# beaglebone.net
KiCad netlist of a schematic drawn in Altium Designer
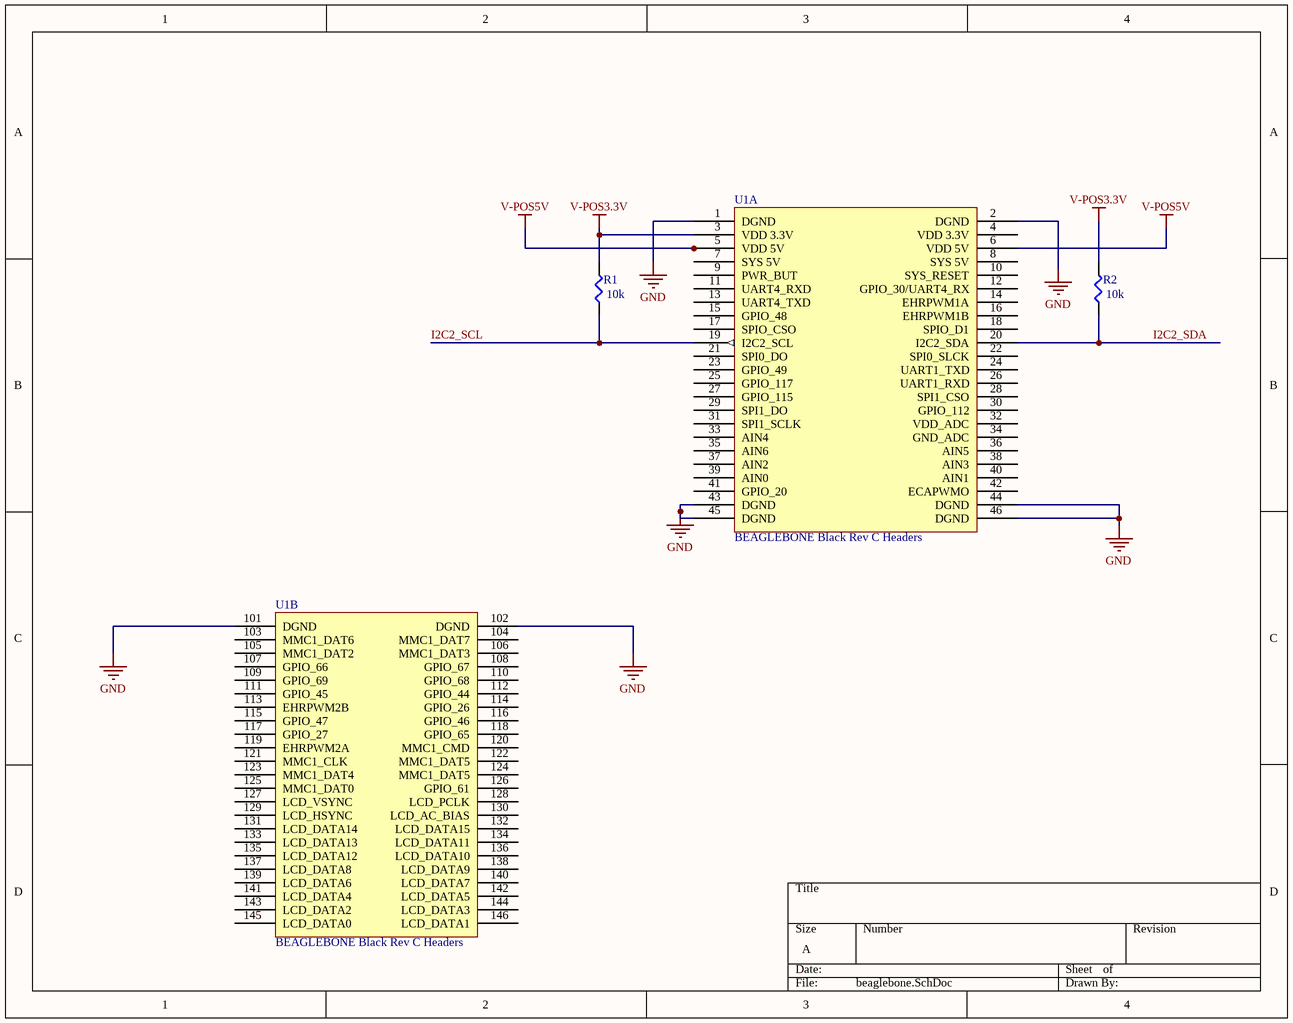
[diagram p0: beaglebone.SchDoc]

(export (version "E")
  (design (tool "Eeschema 10.0.6"))
  (components
    (comp (ref "R1")
      (value "10k")
      (footprint "SMD-0805-RES")
      (description "RES SMD 10K OHM 1% 1/8W 0805")
      (fields
        (field (name "PART NUMBER") "ERJ-6ENF1002V")
        (field (name "DIGI-KEY PART NUMBER") "P10.0KCCT-ND")
      )
      (libsource (lib "resistors") (part "ERJ-6ENF1002V"))
    )
    (comp (ref "R2")
      (value "10k")
      (footprint "SMD-0805-RES")
      (description "RES SMD 10K OHM 1% 1/8W 0805")
      (fields
        (field (name "PART NUMBER") "ERJ-6ENF1002V")
        (field (name "DIGI-KEY PART NUMBER") "P10.0KCCT-ND")
      )
      (libsource (lib "resistors") (part "ERJ-6ENF1002V"))
    )
    (comp (ref "U1")
      (value "BEAGLEBONE Black Rev C Headers")
      (footprint "Beaglebone_Topside")
      (description "KIT DEV BEAGLEBONE BLACK REV C. Header Breakout")
      (libsource (lib "misc") (part "Beaglebone"))
    )
  )
  (nets
    (net (code "1") (name "/I2C2_SCL") (class "Default")
      (node (ref "R1") (pin "1") (pinfunction "1_1") (pintype "passive"))
      (node (ref "U1") (pin "19") (pinfunction "I2C2_SCL_19") (pintype "output"))
    )
    (net (code "2") (name "/I2C2_SDA") (class "Default")
      (node (ref "R2") (pin "1") (pinfunction "1_1") (pintype "passive"))
      (node (ref "U1") (pin "20") (pinfunction "I2C2_SDA_20") (pintype "passive"))
    )
    (net (code "3") (name "GND") (class "Default")
      (node (ref "U1") (pin "1") (pinfunction "DGND_1") (pintype "passive"))
      (node (ref "U1") (pin "101") (pinfunction "DGND_101") (pintype "passive"))
      (node (ref "U1") (pin "102") (pinfunction "DGND_102") (pintype "passive"))
      (node (ref "U1") (pin "2") (pinfunction "DGND_2") (pintype "passive"))
      (node (ref "U1") (pin "43") (pinfunction "DGND_43") (pintype "passive"))
      (node (ref "U1") (pin "44") (pinfunction "DGND_44") (pintype "passive"))
      (node (ref "U1") (pin "45") (pinfunction "DGND_45") (pintype "passive"))
      (node (ref "U1") (pin "46") (pinfunction "DGND_46") (pintype "passive"))
    )
    (net (code "4") (name "V-POS3.3V") (class "Default")
      (node (ref "R1") (pin "2") (pinfunction "2_2") (pintype "passive"))
      (node (ref "R2") (pin "2") (pinfunction "2_2") (pintype "passive"))
      (node (ref "U1") (pin "3") (pinfunction "VDD_3.3V_3") (pintype "passive"))
    )
    (net (code "5") (name "V-POS5V") (class "Default")
      (node (ref "U1") (pin "5") (pinfunction "VDD_5V_5") (pintype "passive"))
      (node (ref "U1") (pin "6") (pinfunction "VDD_5V_6") (pintype "passive"))
    )
    (net (code "6") (name "unconnected-(U1A-AIN0-Pad39)") (class "Default")
      (node (ref "U1") (pin "39") (pinfunction "AIN0_39") (pintype "passive"))
    )
    (net (code "7") (name "unconnected-(U1A-AIN1-Pad40)") (class "Default")
      (node (ref "U1") (pin "40") (pinfunction "AIN1_40") (pintype "passive"))
    )
    (net (code "8") (name "unconnected-(U1A-AIN2-Pad37)") (class "Default")
      (node (ref "U1") (pin "37") (pinfunction "AIN2_37") (pintype "passive"))
    )
    (net (code "9") (name "unconnected-(U1A-AIN3-Pad38)") (class "Default")
      (node (ref "U1") (pin "38") (pinfunction "AIN3_38") (pintype "passive"))
    )
    (net (code "10") (name "unconnected-(U1A-AIN4-Pad33)") (class "Default")
      (node (ref "U1") (pin "33") (pinfunction "AIN4_33") (pintype "passive"))
    )
    (net (code "11") (name "unconnected-(U1A-AIN5-Pad36)") (class "Default")
      (node (ref "U1") (pin "36") (pinfunction "AIN5_36") (pintype "passive"))
    )
    (net (code "12") (name "unconnected-(U1A-AIN6-Pad35)") (class "Default")
      (node (ref "U1") (pin "35") (pinfunction "AIN6_35") (pintype "passive"))
    )
    (net (code "13") (name "unconnected-(U1A-ECAPWMO-Pad42)") (class "Default")
      (node (ref "U1") (pin "42") (pinfunction "ECAPWMO_42") (pintype "passive"))
    )
    (net (code "14") (name "unconnected-(U1A-EHRPWM1A-Pad14)") (class "Default")
      (node (ref "U1") (pin "14") (pinfunction "EHRPWM1A_14") (pintype "passive"))
    )
    (net (code "15") (name "unconnected-(U1A-EHRPWM1B-Pad16)") (class "Default")
      (node (ref "U1") (pin "16") (pinfunction "EHRPWM1B_16") (pintype "passive"))
    )
    (net (code "16") (name "unconnected-(U1A-GND_ADC-Pad34)") (class "Default")
      (node (ref "U1") (pin "34") (pinfunction "GND_ADC_34") (pintype "passive"))
    )
    (net (code "17") (name "unconnected-(U1A-GPIO_20-Pad41)") (class "Default")
      (node (ref "U1") (pin "41") (pinfunction "GPIO_20_41") (pintype "passive"))
    )
    (net (code "18") (name "unconnected-(U1A-GPIO_30{slash}UART4_RX-Pad12)") (class "Default")
      (node (ref "U1") (pin "12") (pinfunction "GPIO_30/UART4_RX_12") (pintype "passive"))
    )
    (net (code "19") (name "unconnected-(U1A-GPIO_48-Pad15)") (class "Default")
      (node (ref "U1") (pin "15") (pinfunction "GPIO_48_15") (pintype "passive"))
    )
    (net (code "20") (name "unconnected-(U1A-GPIO_49-Pad23)") (class "Default")
      (node (ref "U1") (pin "23") (pinfunction "GPIO_49_23") (pintype "passive"))
    )
    (net (code "21") (name "unconnected-(U1A-GPIO_112-Pad30)") (class "Default")
      (node (ref "U1") (pin "30") (pinfunction "GPIO_112_30") (pintype "passive"))
    )
    (net (code "22") (name "unconnected-(U1A-GPIO_115-Pad27)") (class "Default")
      (node (ref "U1") (pin "27") (pinfunction "GPIO_115_27") (pintype "passive"))
    )
    (net (code "23") (name "unconnected-(U1A-GPIO_117-Pad25)") (class "Default")
      (node (ref "U1") (pin "25") (pinfunction "GPIO_117_25") (pintype "passive"))
    )
    (net (code "24") (name "unconnected-(U1A-PWR_BUT-Pad9)") (class "Default")
      (node (ref "U1") (pin "9") (pinfunction "PWR_BUT_9") (pintype "passive"))
    )
    (net (code "25") (name "unconnected-(U1A-SPI0_DO-Pad21)") (class "Default")
      (node (ref "U1") (pin "21") (pinfunction "SPI0_DO_21") (pintype "passive"))
    )
    (net (code "26") (name "unconnected-(U1A-SPI0_SLCK-Pad22)") (class "Default")
      (node (ref "U1") (pin "22") (pinfunction "SPI0_SLCK_22") (pintype "passive"))
    )
    (net (code "27") (name "unconnected-(U1A-SPI1_CSO-Pad28)") (class "Default")
      (node (ref "U1") (pin "28") (pinfunction "SPI1_CSO_28") (pintype "passive"))
    )
    (net (code "28") (name "unconnected-(U1A-SPI1_DO-Pad29)") (class "Default")
      (node (ref "U1") (pin "29") (pinfunction "SPI1_DO_29") (pintype "passive"))
    )
    (net (code "29") (name "unconnected-(U1A-SPI1_SCLK-Pad31)") (class "Default")
      (node (ref "U1") (pin "31") (pinfunction "SPI1_SCLK_31") (pintype "passive"))
    )
    (net (code "30") (name "unconnected-(U1A-SPIO_CSO-Pad17)") (class "Default")
      (node (ref "U1") (pin "17") (pinfunction "SPIO_CSO_17") (pintype "passive"))
    )
    (net (code "31") (name "unconnected-(U1A-SPIO_D1-Pad18)") (class "Default")
      (node (ref "U1") (pin "18") (pinfunction "SPIO_D1_18") (pintype "passive"))
    )
    (net (code "32") (name "unconnected-(U1A-SYS_5V-Pad7)") (class "Default")
      (node (ref "U1") (pin "7") (pinfunction "SYS_5V_7") (pintype "passive"))
    )
    (net (code "33") (name "unconnected-(U1A-SYS_5V-Pad8)") (class "Default")
      (node (ref "U1") (pin "8") (pinfunction "SYS_5V_8") (pintype "passive"))
    )
    (net (code "34") (name "unconnected-(U1A-SYS_RESET-Pad10)") (class "Default")
      (node (ref "U1") (pin "10") (pinfunction "SYS_RESET_10") (pintype "passive"))
    )
    (net (code "35") (name "unconnected-(U1A-UART1_RXD-Pad26)") (class "Default")
      (node (ref "U1") (pin "26") (pinfunction "UART1_RXD_26") (pintype "passive"))
    )
    (net (code "36") (name "unconnected-(U1A-UART1_TXD-Pad24)") (class "Default")
      (node (ref "U1") (pin "24") (pinfunction "UART1_TXD_24") (pintype "passive"))
    )
    (net (code "37") (name "unconnected-(U1A-UART4_RXD-Pad11)") (class "Default")
      (node (ref "U1") (pin "11") (pinfunction "UART4_RXD_11") (pintype "passive"))
    )
    (net (code "38") (name "unconnected-(U1A-UART4_TXD-Pad13)") (class "Default")
      (node (ref "U1") (pin "13") (pinfunction "UART4_TXD_13") (pintype "passive"))
    )
    (net (code "39") (name "unconnected-(U1A-VDD_3.3V-Pad4)") (class "Default")
      (node (ref "U1") (pin "4") (pinfunction "VDD_3.3V_4") (pintype "passive"))
    )
    (net (code "40") (name "unconnected-(U1A-VDD_ADC-Pad32)") (class "Default")
      (node (ref "U1") (pin "32") (pinfunction "VDD_ADC_32") (pintype "passive"))
    )
    (net (code "41") (name "unconnected-(U1B-EHRPWM2A-Pad119)") (class "Default")
      (node (ref "U1") (pin "119") (pinfunction "EHRPWM2A_119") (pintype "passive"))
    )
    (net (code "42") (name "unconnected-(U1B-EHRPWM2B-Pad113)") (class "Default")
      (node (ref "U1") (pin "113") (pinfunction "EHRPWM2B_113") (pintype "passive"))
    )
    (net (code "43") (name "unconnected-(U1B-GPIO_26-Pad114)") (class "Default")
      (node (ref "U1") (pin "114") (pinfunction "GPIO_26_114") (pintype "passive"))
    )
    (net (code "44") (name "unconnected-(U1B-GPIO_27-Pad117)") (class "Default")
      (node (ref "U1") (pin "117") (pinfunction "GPIO_27_117") (pintype "passive"))
    )
    (net (code "45") (name "unconnected-(U1B-GPIO_44-Pad112)") (class "Default")
      (node (ref "U1") (pin "112") (pinfunction "GPIO_44_112") (pintype "passive"))
    )
    (net (code "46") (name "unconnected-(U1B-GPIO_45-Pad111)") (class "Default")
      (node (ref "U1") (pin "111") (pinfunction "GPIO_45_111") (pintype "passive"))
    )
    (net (code "47") (name "unconnected-(U1B-GPIO_46-Pad116)") (class "Default")
      (node (ref "U1") (pin "116") (pinfunction "GPIO_46_116") (pintype "passive"))
    )
    (net (code "48") (name "unconnected-(U1B-GPIO_47-Pad115)") (class "Default")
      (node (ref "U1") (pin "115") (pinfunction "GPIO_47_115") (pintype "passive"))
    )
    (net (code "49") (name "unconnected-(U1B-GPIO_61-Pad126)") (class "Default")
      (node (ref "U1") (pin "126") (pinfunction "GPIO_61_126") (pintype "passive"))
    )
    (net (code "50") (name "unconnected-(U1B-GPIO_65-Pad118)") (class "Default")
      (node (ref "U1") (pin "118") (pinfunction "GPIO_65_118") (pintype "passive"))
    )
    (net (code "51") (name "unconnected-(U1B-GPIO_66-Pad107)") (class "Default")
      (node (ref "U1") (pin "107") (pinfunction "GPIO_66_107") (pintype "passive"))
    )
    (net (code "52") (name "unconnected-(U1B-GPIO_67-Pad108)") (class "Default")
      (node (ref "U1") (pin "108") (pinfunction "GPIO_67_108") (pintype "passive"))
    )
    (net (code "53") (name "unconnected-(U1B-GPIO_68-Pad110)") (class "Default")
      (node (ref "U1") (pin "110") (pinfunction "GPIO_68_110") (pintype "passive"))
    )
    (net (code "54") (name "unconnected-(U1B-GPIO_69-Pad109)") (class "Default")
      (node (ref "U1") (pin "109") (pinfunction "GPIO_69_109") (pintype "passive"))
    )
    (net (code "55") (name "unconnected-(U1B-LCD_AC_BIAS-Pad130)") (class "Default")
      (node (ref "U1") (pin "130") (pinfunction "LCD_AC_BIAS_130") (pintype "passive"))
    )
    (net (code "56") (name "unconnected-(U1B-LCD_DATA0-Pad145)") (class "Default")
      (node (ref "U1") (pin "145") (pinfunction "LCD_DATA0_145") (pintype "passive"))
    )
    (net (code "57") (name "unconnected-(U1B-LCD_DATA1-Pad146)") (class "Default")
      (node (ref "U1") (pin "146") (pinfunction "LCD_DATA1_146") (pintype "passive"))
    )
    (net (code "58") (name "unconnected-(U1B-LCD_DATA2-Pad143)") (class "Default")
      (node (ref "U1") (pin "143") (pinfunction "LCD_DATA2_143") (pintype "passive"))
    )
    (net (code "59") (name "unconnected-(U1B-LCD_DATA3-Pad144)") (class "Default")
      (node (ref "U1") (pin "144") (pinfunction "LCD_DATA3_144") (pintype "passive"))
    )
    (net (code "60") (name "unconnected-(U1B-LCD_DATA4-Pad141)") (class "Default")
      (node (ref "U1") (pin "141") (pinfunction "LCD_DATA4_141") (pintype "passive"))
    )
    (net (code "61") (name "unconnected-(U1B-LCD_DATA5-Pad142)") (class "Default")
      (node (ref "U1") (pin "142") (pinfunction "LCD_DATA5_142") (pintype "passive"))
    )
    (net (code "62") (name "unconnected-(U1B-LCD_DATA6-Pad139)") (class "Default")
      (node (ref "U1") (pin "139") (pinfunction "LCD_DATA6_139") (pintype "passive"))
    )
    (net (code "63") (name "unconnected-(U1B-LCD_DATA7-Pad140)") (class "Default")
      (node (ref "U1") (pin "140") (pinfunction "LCD_DATA7_140") (pintype "passive"))
    )
    (net (code "64") (name "unconnected-(U1B-LCD_DATA8-Pad137)") (class "Default")
      (node (ref "U1") (pin "137") (pinfunction "LCD_DATA8_137") (pintype "passive"))
    )
    (net (code "65") (name "unconnected-(U1B-LCD_DATA9-Pad138)") (class "Default")
      (node (ref "U1") (pin "138") (pinfunction "LCD_DATA9_138") (pintype "passive"))
    )
    (net (code "66") (name "unconnected-(U1B-LCD_DATA10-Pad136)") (class "Default")
      (node (ref "U1") (pin "136") (pinfunction "LCD_DATA10_136") (pintype "passive"))
    )
    (net (code "67") (name "unconnected-(U1B-LCD_DATA11-Pad134)") (class "Default")
      (node (ref "U1") (pin "134") (pinfunction "LCD_DATA11_134") (pintype "passive"))
    )
    (net (code "68") (name "unconnected-(U1B-LCD_DATA12-Pad135)") (class "Default")
      (node (ref "U1") (pin "135") (pinfunction "LCD_DATA12_135") (pintype "passive"))
    )
    (net (code "69") (name "unconnected-(U1B-LCD_DATA13-Pad133)") (class "Default")
      (node (ref "U1") (pin "133") (pinfunction "LCD_DATA13_133") (pintype "passive"))
    )
    (net (code "70") (name "unconnected-(U1B-LCD_DATA14-Pad131)") (class "Default")
      (node (ref "U1") (pin "131") (pinfunction "LCD_DATA14_131") (pintype "passive"))
    )
    (net (code "71") (name "unconnected-(U1B-LCD_DATA15-Pad132)") (class "Default")
      (node (ref "U1") (pin "132") (pinfunction "LCD_DATA15_132") (pintype "passive"))
    )
    (net (code "72") (name "unconnected-(U1B-LCD_HSYNC-Pad129)") (class "Default")
      (node (ref "U1") (pin "129") (pinfunction "LCD_HSYNC_129") (pintype "passive"))
    )
    (net (code "73") (name "unconnected-(U1B-LCD_PCLK-Pad128)") (class "Default")
      (node (ref "U1") (pin "128") (pinfunction "LCD_PCLK_128") (pintype "passive"))
    )
    (net (code "74") (name "unconnected-(U1B-LCD_VSYNC-Pad127)") (class "Default")
      (node (ref "U1") (pin "127") (pinfunction "LCD_VSYNC_127") (pintype "passive"))
    )
    (net (code "75") (name "unconnected-(U1B-MMC1_CLK-Pad121)") (class "Default")
      (node (ref "U1") (pin "121") (pinfunction "MMC1_CLK_121") (pintype "passive"))
    )
    (net (code "76") (name "unconnected-(U1B-MMC1_CMD-Pad120)") (class "Default")
      (node (ref "U1") (pin "120") (pinfunction "MMC1_CMD_120") (pintype "passive"))
    )
    (net (code "77") (name "unconnected-(U1B-MMC1_DAT0-Pad125)") (class "Default")
      (node (ref "U1") (pin "125") (pinfunction "MMC1_DAT0_125") (pintype "passive"))
    )
    (net (code "78") (name "unconnected-(U1B-MMC1_DAT2-Pad105)") (class "Default")
      (node (ref "U1") (pin "105") (pinfunction "MMC1_DAT2_105") (pintype "passive"))
    )
    (net (code "79") (name "unconnected-(U1B-MMC1_DAT3-Pad106)") (class "Default")
      (node (ref "U1") (pin "106") (pinfunction "MMC1_DAT3_106") (pintype "passive"))
    )
    (net (code "80") (name "unconnected-(U1B-MMC1_DAT4-Pad123)") (class "Default")
      (node (ref "U1") (pin "123") (pinfunction "MMC1_DAT4_123") (pintype "passive"))
    )
    (net (code "81") (name "unconnected-(U1B-MMC1_DAT5-Pad122)") (class "Default")
      (node (ref "U1") (pin "122") (pinfunction "MMC1_DAT5_122") (pintype "passive"))
    )
    (net (code "82") (name "unconnected-(U1B-MMC1_DAT5-Pad124)") (class "Default")
      (node (ref "U1") (pin "124") (pinfunction "MMC1_DAT5_124") (pintype "passive"))
    )
    (net (code "83") (name "unconnected-(U1B-MMC1_DAT6-Pad103)") (class "Default")
      (node (ref "U1") (pin "103") (pinfunction "MMC1_DAT6_103") (pintype "passive"))
    )
    (net (code "84") (name "unconnected-(U1B-MMC1_DAT7-Pad104)") (class "Default")
      (node (ref "U1") (pin "104") (pinfunction "MMC1_DAT7_104") (pintype "passive"))
    )
  )
)
